# quantizer-main.net
KiCad netlist of a schematic drawn in EAGLE
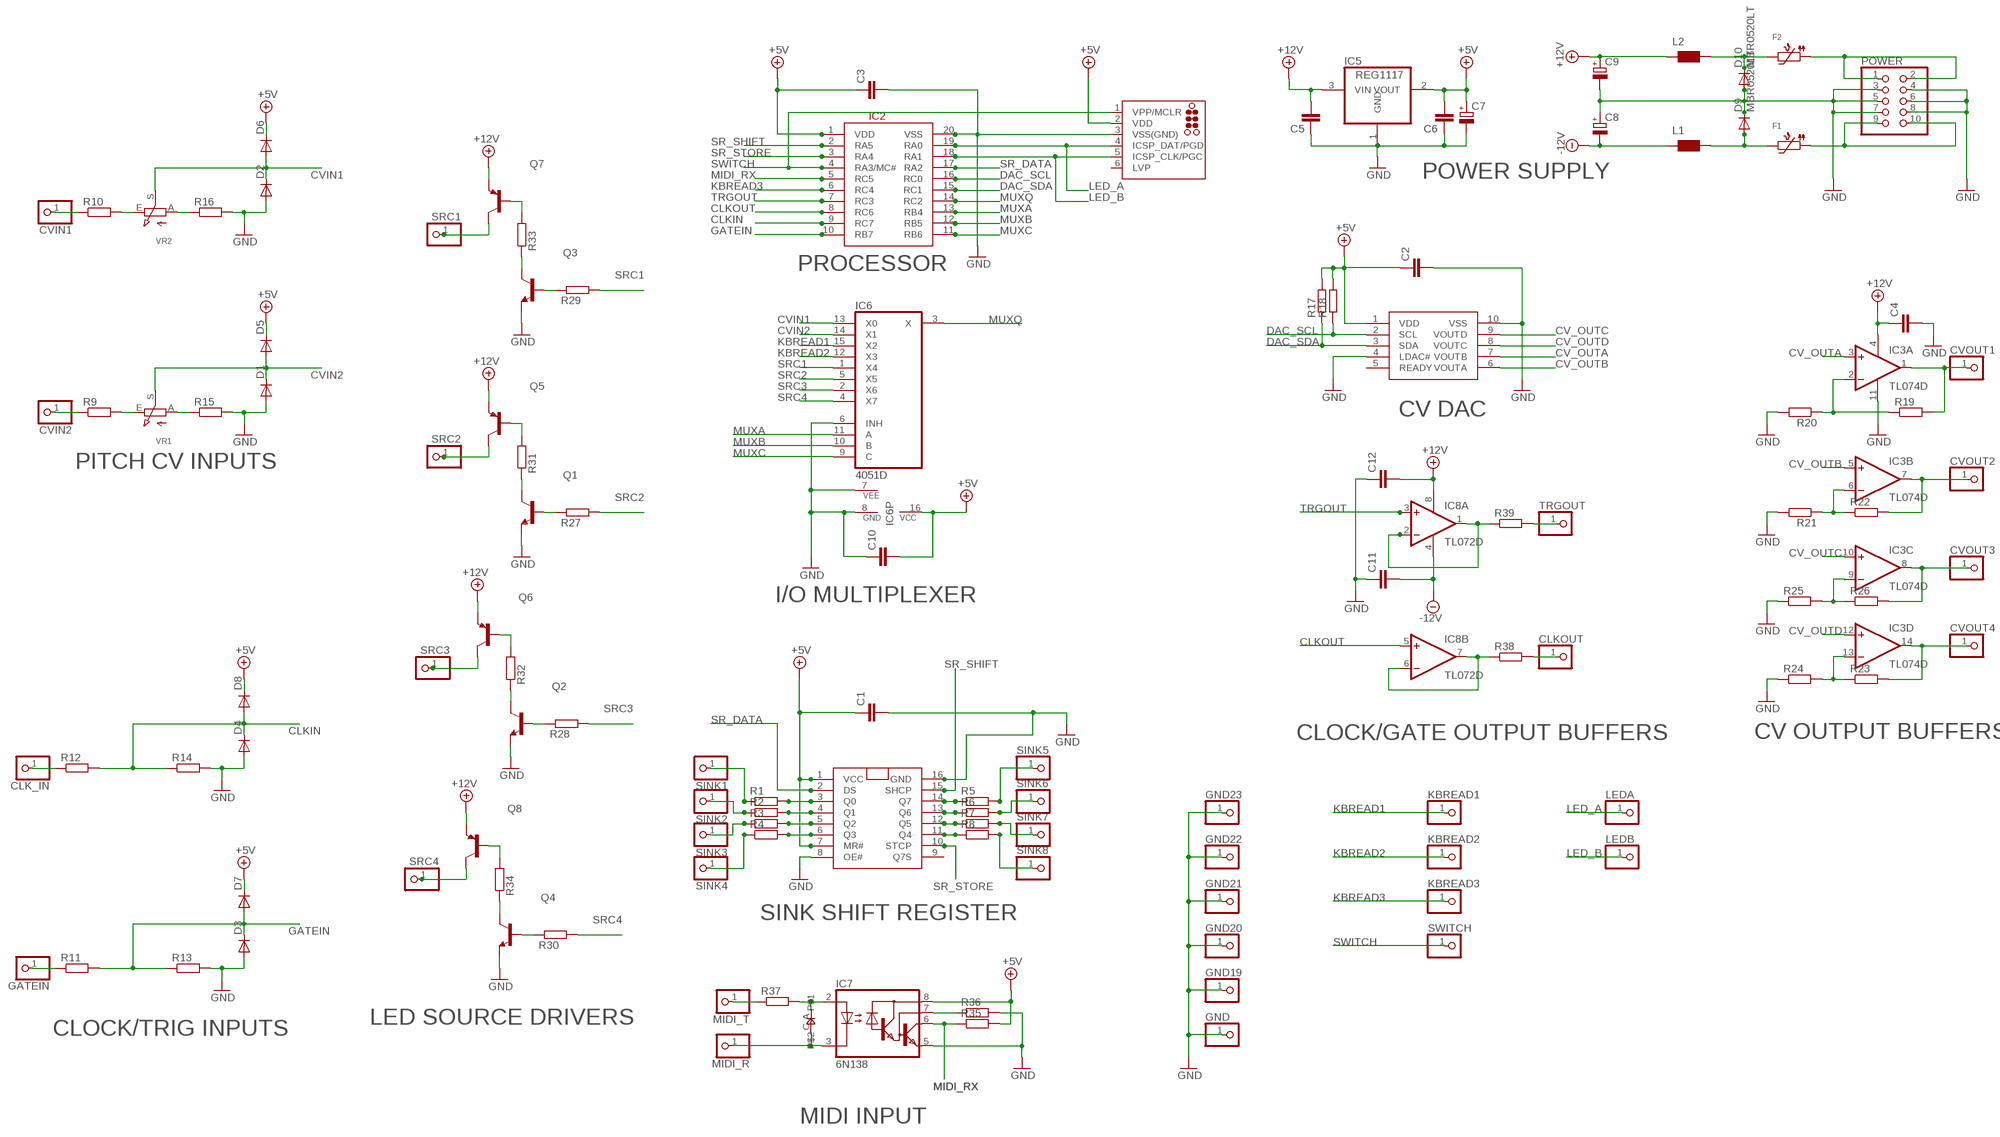
[diagram p0: schematic, sheet 1]

(export (version "E")
  (design (tool "Eeschema 10.0.6"))
  (components
    (comp (ref "C1")
      (value "C-EUC0805")
      (footprint "eagle-import:C0805")
      (libsource (lib "eagle-import") (part "C-EUC0805"))
    )
    (comp (ref "C2")
      (value "C-EUC0805")
      (footprint "eagle-import:C0805")
      (libsource (lib "eagle-import") (part "C-EUC0805"))
    )
    (comp (ref "C3")
      (value "C-EUC0805")
      (footprint "eagle-import:C0805")
      (libsource (lib "eagle-import") (part "C-EUC0805"))
    )
    (comp (ref "C4")
      (value "C-EUC0805")
      (footprint "eagle-import:C0805")
      (libsource (lib "eagle-import") (part "C-EUC0805"))
    )
    (comp (ref "C5")
      (value "C-EUC0805")
      (footprint "eagle-import:C0805")
      (libsource (lib "eagle-import") (part "C-EUC0805"))
    )
    (comp (ref "C6")
      (value "C-EUC0805")
      (footprint "eagle-import:C0805")
      (libsource (lib "eagle-import") (part "C-EUC0805"))
    )
    (comp (ref "C7")
      (value "CPOL-EUE2.5-5")
      (footprint "eagle-import:E2,5-5")
      (libsource (lib "eagle-import") (part "CPOL-EUE2.5-5"))
    )
    (comp (ref "C8")
      (value "CPOL-EUE2.5-7")
      (footprint "eagle-import:E2,5-7")
      (libsource (lib "eagle-import") (part "CPOL-EUE2.5-7"))
    )
    (comp (ref "C9")
      (value "CPOL-EUE2.5-7")
      (footprint "eagle-import:E2,5-7")
      (libsource (lib "eagle-import") (part "CPOL-EUE2.5-7"))
    )
    (comp (ref "C10")
      (value "C-EUC0805")
      (footprint "eagle-import:C0805")
      (libsource (lib "eagle-import") (part "C-EUC0805"))
    )
    (comp (ref "C11")
      (value "C-EUC0805")
      (footprint "eagle-import:C0805")
      (libsource (lib "eagle-import") (part "C-EUC0805"))
    )
    (comp (ref "C12")
      (value "C-EUC0805")
      (footprint "eagle-import:C0805")
      (libsource (lib "eagle-import") (part "C-EUC0805"))
    )
    (comp (ref "CLKOUT")
      (value "PINHD-1X1")
      (footprint "eagle-import:1X01")
      (libsource (lib "eagle-import") (part "PINHD-1X1"))
    )
    (comp (ref "CLK_IN")
      (value "PINHD-1X1")
      (footprint "eagle-import:1X01")
      (libsource (lib "eagle-import") (part "PINHD-1X1"))
    )
    (comp (ref "CVIN1")
      (value "PINHD-1X1")
      (footprint "eagle-import:1X01")
      (libsource (lib "eagle-import") (part "PINHD-1X1"))
    )
    (comp (ref "CVIN2")
      (value "PINHD-1X1")
      (footprint "eagle-import:1X01")
      (libsource (lib "eagle-import") (part "PINHD-1X1"))
    )
    (comp (ref "CVOUT1")
      (value "PINHD-1X1")
      (footprint "eagle-import:1X01")
      (libsource (lib "eagle-import") (part "PINHD-1X1"))
    )
    (comp (ref "CVOUT2")
      (value "PINHD-1X1")
      (footprint "eagle-import:1X01")
      (libsource (lib "eagle-import") (part "PINHD-1X1"))
    )
    (comp (ref "CVOUT3")
      (value "PINHD-1X1")
      (footprint "eagle-import:1X01")
      (libsource (lib "eagle-import") (part "PINHD-1X1"))
    )
    (comp (ref "CVOUT4")
      (value "PINHD-1X1")
      (footprint "eagle-import:1X01")
      (libsource (lib "eagle-import") (part "PINHD-1X1"))
    )
    (comp (ref "D1")
      (value "DIODE-SOD123")
      (footprint "eagle-import:SOD123")
      (libsource (lib "eagle-import") (part "DIODE-SOD123"))
    )
    (comp (ref "D2")
      (value "DIODE-SOD123")
      (footprint "eagle-import:SOD123")
      (libsource (lib "eagle-import") (part "DIODE-SOD123"))
    )
    (comp (ref "D3")
      (value "DIODE-SOD123")
      (footprint "eagle-import:SOD123")
      (libsource (lib "eagle-import") (part "DIODE-SOD123"))
    )
    (comp (ref "D4")
      (value "DIODE-SOD123")
      (footprint "eagle-import:SOD123")
      (libsource (lib "eagle-import") (part "DIODE-SOD123"))
    )
    (comp (ref "D5")
      (value "DIODE-SOD123")
      (footprint "eagle-import:SOD123")
      (libsource (lib "eagle-import") (part "DIODE-SOD123"))
    )
    (comp (ref "D6")
      (value "DIODE-SOD123")
      (footprint "eagle-import:SOD123")
      (libsource (lib "eagle-import") (part "DIODE-SOD123"))
    )
    (comp (ref "D7")
      (value "DIODE-SOD123")
      (footprint "eagle-import:SOD123")
      (libsource (lib "eagle-import") (part "DIODE-SOD123"))
    )
    (comp (ref "D8")
      (value "DIODE-SOD123")
      (footprint "eagle-import:SOD123")
      (libsource (lib "eagle-import") (part "DIODE-SOD123"))
    )
    (comp (ref "D9")
      (value "MBR0520LT")
      (footprint "eagle-import:SOD123")
      (libsource (lib "eagle-import") (part "MBR0520LT"))
    )
    (comp (ref "D10")
      (value "MBR0520LT")
      (footprint "eagle-import:SOD123")
      (libsource (lib "eagle-import") (part "MBR0520LT"))
    )
    (comp (ref "D11")
      (value "0805DIODE")
      (footprint "eagle-import:0805DIODE")
      (libsource (lib "eagle-import") (part "0805DIODE"))
    )
    (comp (ref "F1")
      (value "PTC1210")
      (footprint "eagle-import:PTC1210")
      (libsource (lib "eagle-import") (part "PTC1210"))
    )
    (comp (ref "F2")
      (value "PTC1210")
      (footprint "eagle-import:PTC1210")
      (libsource (lib "eagle-import") (part "PTC1210"))
    )
    (comp (ref "GATEIN")
      (value "PINHD-1X1")
      (footprint "eagle-import:1X01")
      (libsource (lib "eagle-import") (part "PINHD-1X1"))
    )
    (comp (ref "GND")
      (value "PINHD-1X1")
      (footprint "eagle-import:1X01")
      (libsource (lib "eagle-import") (part "PINHD-1X1"))
    )
    (comp (ref "GND19")
      (value "PINHD-1X1")
      (footprint "eagle-import:1X01")
      (libsource (lib "eagle-import") (part "PINHD-1X1"))
    )
    (comp (ref "GND20")
      (value "PINHD-1X1")
      (footprint "eagle-import:1X01")
      (libsource (lib "eagle-import") (part "PINHD-1X1"))
    )
    (comp (ref "GND21")
      (value "PINHD-1X1")
      (footprint "eagle-import:1X01")
      (libsource (lib "eagle-import") (part "PINHD-1X1"))
    )
    (comp (ref "GND22")
      (value "PINHD-1X1")
      (footprint "eagle-import:1X01")
      (libsource (lib "eagle-import") (part "PINHD-1X1"))
    )
    (comp (ref "GND23")
      (value "PINHD-1X1")
      (footprint "eagle-import:1X01")
      (libsource (lib "eagle-import") (part "PINHD-1X1"))
    )
    (comp (ref "IC1")
      (value "NPIC6C596")
      (footprint "eagle-import:SO16")
      (libsource (lib "eagle-import") (part "NPIC6C596"))
    )
    (comp (ref "IC2")
      (value "PIC16F1829SOIC")
      (footprint "eagle-import:SO20W")
      (libsource (lib "eagle-import") (part "PIC16F1829SOIC"))
    )
    (comp (ref "IC3")
      (value "TL074D")
      (footprint "eagle-import:SO14")
      (libsource (lib "eagle-import") (part "TL074D"))
    )
    (comp (ref "IC4")
      (value "MCP4728_QUAD_DAC")
      (footprint "eagle-import:MSOP10")
      (libsource (lib "eagle-import") (part "MCP4728_QUAD_DAC"))
    )
    (comp (ref "IC5")
      (value "REG1117")
      (footprint "eagle-import:SOT223")
      (libsource (lib "eagle-import") (part "REG1117"))
    )
    (comp (ref "IC6")
      (value "4051D")
      (footprint "eagle-import:SO16")
      (libsource (lib "eagle-import") (part "4051D"))
    )
    (comp (ref "IC7")
      (value "6N138")
      (footprint "eagle-import:DIL08")
      (fields (field (name "MF") "VISHAY/TELEFUNKEN"))
      (libsource (lib "eagle-import") (part "6N138"))
    )
    (comp (ref "IC8")
      (value "TL072D")
      (footprint "eagle-import:SO08")
      (libsource (lib "eagle-import") (part "TL072D"))
    )
    (comp (ref "J1")
      (value "TC2030-MCP-NL")
      (footprint "eagle-import:TC2030-MCP-NL")
      (libsource (lib "eagle-import") (part "TC2030-MCP-NL"))
    )
    (comp (ref "KBREAD1")
      (value "PINHD-1X1")
      (footprint "eagle-import:1X01")
      (libsource (lib "eagle-import") (part "PINHD-1X1"))
    )
    (comp (ref "KBREAD2")
      (value "PINHD-1X1")
      (footprint "eagle-import:1X01")
      (libsource (lib "eagle-import") (part "PINHD-1X1"))
    )
    (comp (ref "KBREAD3")
      (value "PINHD-1X1")
      (footprint "eagle-import:1X01")
      (libsource (lib "eagle-import") (part "PINHD-1X1"))
    )
    (comp (ref "L1")
      (value "WE-CBF_0805")
      (footprint "eagle-import:0805")
      (libsource (lib "eagle-import") (part "WE-CBF_0805"))
    )
    (comp (ref "L2")
      (value "WE-CBF_0805")
      (footprint "eagle-import:0805")
      (libsource (lib "eagle-import") (part "WE-CBF_0805"))
    )
    (comp (ref "LEDA")
      (value "PINHD-1X1")
      (footprint "eagle-import:1X01")
      (libsource (lib "eagle-import") (part "PINHD-1X1"))
    )
    (comp (ref "LEDB")
      (value "PINHD-1X1")
      (footprint "eagle-import:1X01")
      (libsource (lib "eagle-import") (part "PINHD-1X1"))
    )
    (comp (ref "MIDI_R")
      (value "PINHD-1X1")
      (footprint "eagle-import:1X01")
      (libsource (lib "eagle-import") (part "PINHD-1X1"))
    )
    (comp (ref "MIDI_T")
      (value "PINHD-1X1")
      (footprint "eagle-import:1X01")
      (libsource (lib "eagle-import") (part "PINHD-1X1"))
    )
    (comp (ref "POWER")
      (value "PINHD-2X5")
      (footprint "eagle-import:2X05")
      (libsource (lib "eagle-import") (part "PINHD-2X5"))
    )
    (comp (ref "Q1")
      (value "MMBT3904LT1-NPN-SOT23-BEC")
      (footprint "eagle-import:SOT23-BEC")
      (libsource (lib "eagle-import") (part "-NPN-SOT23-BECMMBT3904LT1"))
    )
    (comp (ref "Q2")
      (value "MMBT3904LT1-NPN-SOT23-BEC")
      (footprint "eagle-import:SOT23-BEC")
      (libsource (lib "eagle-import") (part "-NPN-SOT23-BECMMBT3904LT1"))
    )
    (comp (ref "Q3")
      (value "MMBT3904LT1-NPN-SOT23-BEC")
      (footprint "eagle-import:SOT23-BEC")
      (libsource (lib "eagle-import") (part "-NPN-SOT23-BECMMBT3904LT1"))
    )
    (comp (ref "Q4")
      (value "MMBT3904LT1-NPN-SOT23-BEC")
      (footprint "eagle-import:SOT23-BEC")
      (libsource (lib "eagle-import") (part "-NPN-SOT23-BECMMBT3904LT1"))
    )
    (comp (ref "Q5")
      (value "MMBT3906LT1-PNP-SOT23-BEC")
      (footprint "eagle-import:SOT23-BEC")
      (libsource (lib "eagle-import") (part "-PNP-SOT23-BECMMBT3906LT1"))
    )
    (comp (ref "Q6")
      (value "MMBT3906LT1-PNP-SOT23-BEC")
      (footprint "eagle-import:SOT23-BEC")
      (libsource (lib "eagle-import") (part "-PNP-SOT23-BECMMBT3906LT1"))
    )
    (comp (ref "Q7")
      (value "MMBT3906LT1-PNP-SOT23-BEC")
      (footprint "eagle-import:SOT23-BEC")
      (libsource (lib "eagle-import") (part "-PNP-SOT23-BECMMBT3906LT1"))
    )
    (comp (ref "Q8")
      (value "MMBT3906LT1-PNP-SOT23-BEC")
      (footprint "eagle-import:SOT23-BEC")
      (libsource (lib "eagle-import") (part "-PNP-SOT23-BECMMBT3906LT1"))
    )
    (comp (ref "R1")
      (value "R-EU_R0805")
      (footprint "eagle-import:R0805")
      (libsource (lib "eagle-import") (part "R-EU_R0805"))
    )
    (comp (ref "R2")
      (value "R-EU_R0805")
      (footprint "eagle-import:R0805")
      (libsource (lib "eagle-import") (part "R-EU_R0805"))
    )
    (comp (ref "R3")
      (value "R-EU_R0805")
      (footprint "eagle-import:R0805")
      (libsource (lib "eagle-import") (part "R-EU_R0805"))
    )
    (comp (ref "R4")
      (value "R-EU_R0805")
      (footprint "eagle-import:R0805")
      (libsource (lib "eagle-import") (part "R-EU_R0805"))
    )
    (comp (ref "R5")
      (value "R-EU_R0805")
      (footprint "eagle-import:R0805")
      (libsource (lib "eagle-import") (part "R-EU_R0805"))
    )
    (comp (ref "R6")
      (value "R-EU_R0805")
      (footprint "eagle-import:R0805")
      (libsource (lib "eagle-import") (part "R-EU_R0805"))
    )
    (comp (ref "R7")
      (value "R-EU_R0805")
      (footprint "eagle-import:R0805")
      (libsource (lib "eagle-import") (part "R-EU_R0805"))
    )
    (comp (ref "R8")
      (value "R-EU_R0805")
      (footprint "eagle-import:R0805")
      (libsource (lib "eagle-import") (part "R-EU_R0805"))
    )
    (comp (ref "R9")
      (value "R-EU_R0805")
      (footprint "eagle-import:R0805")
      (libsource (lib "eagle-import") (part "R-EU_R0805"))
    )
    (comp (ref "R10")
      (value "R-EU_R0805")
      (footprint "eagle-import:R0805")
      (libsource (lib "eagle-import") (part "R-EU_R0805"))
    )
    (comp (ref "R11")
      (value "R-EU_R0805")
      (footprint "eagle-import:R0805")
      (libsource (lib "eagle-import") (part "R-EU_R0805"))
    )
    (comp (ref "R12")
      (value "R-EU_R0805")
      (footprint "eagle-import:R0805")
      (libsource (lib "eagle-import") (part "R-EU_R0805"))
    )
    (comp (ref "R13")
      (value "R-EU_R0805")
      (footprint "eagle-import:R0805")
      (libsource (lib "eagle-import") (part "R-EU_R0805"))
    )
    (comp (ref "R14")
      (value "R-EU_R0805")
      (footprint "eagle-import:R0805")
      (libsource (lib "eagle-import") (part "R-EU_R0805"))
    )
    (comp (ref "R15")
      (value "R-EU_R0805")
      (footprint "eagle-import:R0805")
      (libsource (lib "eagle-import") (part "R-EU_R0805"))
    )
    (comp (ref "R16")
      (value "R-EU_R0805")
      (footprint "eagle-import:R0805")
      (libsource (lib "eagle-import") (part "R-EU_R0805"))
    )
    (comp (ref "R17")
      (value "R-EU_R0805")
      (footprint "eagle-import:R0805")
      (libsource (lib "eagle-import") (part "R-EU_R0805"))
    )
    (comp (ref "R18")
      (value "R-EU_R0805")
      (footprint "eagle-import:R0805")
      (libsource (lib "eagle-import") (part "R-EU_R0805"))
    )
    (comp (ref "R19")
      (value "R-EU_R0805")
      (footprint "eagle-import:R0805")
      (libsource (lib "eagle-import") (part "R-EU_R0805"))
    )
    (comp (ref "R20")
      (value "R-EU_R0805")
      (footprint "eagle-import:R0805")
      (libsource (lib "eagle-import") (part "R-EU_R0805"))
    )
    (comp (ref "R21")
      (value "R-EU_R0805")
      (footprint "eagle-import:R0805")
      (libsource (lib "eagle-import") (part "R-EU_R0805"))
    )
    (comp (ref "R22")
      (value "R-EU_R0805")
      (footprint "eagle-import:R0805")
      (libsource (lib "eagle-import") (part "R-EU_R0805"))
    )
    (comp (ref "R23")
      (value "R-EU_R0805")
      (footprint "eagle-import:R0805")
      (libsource (lib "eagle-import") (part "R-EU_R0805"))
    )
    (comp (ref "R24")
      (value "R-EU_R0805")
      (footprint "eagle-import:R0805")
      (libsource (lib "eagle-import") (part "R-EU_R0805"))
    )
    (comp (ref "R25")
      (value "R-EU_R0805")
      (footprint "eagle-import:R0805")
      (libsource (lib "eagle-import") (part "R-EU_R0805"))
    )
    (comp (ref "R26")
      (value "R-EU_R0805")
      (footprint "eagle-import:R0805")
      (libsource (lib "eagle-import") (part "R-EU_R0805"))
    )
    (comp (ref "R27")
      (value "R-EU_R0805")
      (footprint "eagle-import:R0805")
      (libsource (lib "eagle-import") (part "R-EU_R0805"))
    )
    (comp (ref "R28")
      (value "R-EU_R0805")
      (footprint "eagle-import:R0805")
      (libsource (lib "eagle-import") (part "R-EU_R0805"))
    )
    (comp (ref "R29")
      (value "R-EU_R0805")
      (footprint "eagle-import:R0805")
      (libsource (lib "eagle-import") (part "R-EU_R0805"))
    )
    (comp (ref "R30")
      (value "R-EU_R0805")
      (footprint "eagle-import:R0805")
      (libsource (lib "eagle-import") (part "R-EU_R0805"))
    )
    (comp (ref "R31")
      (value "R-EU_R0805")
      (footprint "eagle-import:R0805")
      (libsource (lib "eagle-import") (part "R-EU_R0805"))
    )
    (comp (ref "R32")
      (value "R-EU_R0805")
      (footprint "eagle-import:R0805")
      (libsource (lib "eagle-import") (part "R-EU_R0805"))
    )
    (comp (ref "R33")
      (value "R-EU_R0805")
      (footprint "eagle-import:R0805")
      (libsource (lib "eagle-import") (part "R-EU_R0805"))
    )
    (comp (ref "R34")
      (value "R-EU_R0805")
      (footprint "eagle-import:R0805")
      (libsource (lib "eagle-import") (part "R-EU_R0805"))
    )
    (comp (ref "R35")
      (value "R-EU_R0805")
      (footprint "eagle-import:R0805")
      (libsource (lib "eagle-import") (part "R-EU_R0805"))
    )
    (comp (ref "R36")
      (value "R-EU_R0805")
      (footprint "eagle-import:R0805")
      (libsource (lib "eagle-import") (part "R-EU_R0805"))
    )
    (comp (ref "R37")
      (value "R-EU_R0805")
      (footprint "eagle-import:R0805")
      (libsource (lib "eagle-import") (part "R-EU_R0805"))
    )
    (comp (ref "R38")
      (value "R-EU_R0805")
      (footprint "eagle-import:R0805")
      (libsource (lib "eagle-import") (part "R-EU_R0805"))
    )
    (comp (ref "R39")
      (value "R-EU_R0805")
      (footprint "eagle-import:R0805")
      (libsource (lib "eagle-import") (part "R-EU_R0805"))
    )
    (comp (ref "SINK1")
      (value "PINHD-1X1")
      (footprint "eagle-import:1X01")
      (libsource (lib "eagle-import") (part "PINHD-1X1"))
    )
    (comp (ref "SINK2")
      (value "PINHD-1X1")
      (footprint "eagle-import:1X01")
      (libsource (lib "eagle-import") (part "PINHD-1X1"))
    )
    (comp (ref "SINK3")
      (value "PINHD-1X1")
      (footprint "eagle-import:1X01")
      (libsource (lib "eagle-import") (part "PINHD-1X1"))
    )
    (comp (ref "SINK4")
      (value "PINHD-1X1")
      (footprint "eagle-import:1X01")
      (libsource (lib "eagle-import") (part "PINHD-1X1"))
    )
    (comp (ref "SINK5")
      (value "PINHD-1X1")
      (footprint "eagle-import:1X01")
      (libsource (lib "eagle-import") (part "PINHD-1X1"))
    )
    (comp (ref "SINK6")
      (value "PINHD-1X1")
      (footprint "eagle-import:1X01")
      (libsource (lib "eagle-import") (part "PINHD-1X1"))
    )
    (comp (ref "SINK7")
      (value "PINHD-1X1")
      (footprint "eagle-import:1X01")
      (libsource (lib "eagle-import") (part "PINHD-1X1"))
    )
    (comp (ref "SINK8")
      (value "PINHD-1X1")
      (footprint "eagle-import:1X01")
      (libsource (lib "eagle-import") (part "PINHD-1X1"))
    )
    (comp (ref "SRC1")
      (value "PINHD-1X1")
      (footprint "eagle-import:1X01")
      (libsource (lib "eagle-import") (part "PINHD-1X1"))
    )
    (comp (ref "SRC2")
      (value "PINHD-1X1")
      (footprint "eagle-import:1X01")
      (libsource (lib "eagle-import") (part "PINHD-1X1"))
    )
    (comp (ref "SRC3")
      (value "PINHD-1X1")
      (footprint "eagle-import:1X01")
      (libsource (lib "eagle-import") (part "PINHD-1X1"))
    )
    (comp (ref "SRC4")
      (value "PINHD-1X1")
      (footprint "eagle-import:1X01")
      (libsource (lib "eagle-import") (part "PINHD-1X1"))
    )
    (comp (ref "SWITCH")
      (value "PINHD-1X1")
      (footprint "eagle-import:1X01")
      (libsource (lib "eagle-import") (part "PINHD-1X1"))
    )
    (comp (ref "TRGOUT")
      (value "PINHD-1X1")
      (footprint "eagle-import:1X01")
      (libsource (lib "eagle-import") (part "PINHD-1X1"))
    )
    (comp (ref "VR1")
      (value "TRIMPOT10K_BOURNS")
      (footprint "eagle-import:TRIMPOT_BOURNS3MM")
      (libsource (lib "eagle-import") (part "TRIMPOT10K_BOURNS"))
    )
    (comp (ref "VR2")
      (value "TRIMPOT10K_BOURNS")
      (footprint "eagle-import:TRIMPOT_BOURNS3MM")
      (libsource (lib "eagle-import") (part "TRIMPOT10K_BOURNS"))
    )
  )
  (nets
    (net (code "1") (name "+5V") (class "Default")
      (node (ref "C1") (pin "1") (pinfunction "1_1") (pintype "passive"))
      (node (ref "C10") (pin "2") (pinfunction "2_2") (pintype "passive"))
      (node (ref "C2") (pin "1") (pinfunction "1_1") (pintype "passive"))
      (node (ref "C3") (pin "1") (pinfunction "1_1") (pintype "passive"))
      (node (ref "C6") (pin "2") (pinfunction "2_2") (pintype "passive"))
      (node (ref "C7") (pin "+") (pinfunction "+_+") (pintype "passive"))
      (node (ref "D5") (pin "C") (pinfunction "C_C") (pintype "passive"))
      (node (ref "D6") (pin "C") (pinfunction "C_C") (pintype "passive"))
      (node (ref "D7") (pin "C") (pinfunction "C_C") (pintype "passive"))
      (node (ref "D8") (pin "C") (pinfunction "C_C") (pintype "passive"))
      (node (ref "IC1") (pin "1") (pinfunction "VCC_1") (pintype "power_in"))
      (node (ref "IC1") (pin "7") (pinfunction "MR#_7") (pintype "input"))
      (node (ref "IC2") (pin "1") (pinfunction "VDD_1") (pintype "power_in"))
      (node (ref "IC4") (pin "1") (pinfunction "VDD_1") (pintype "power_in"))
      (node (ref "IC5") (pin "2") (pinfunction "VOUT_2") (pintype "output"))
      (node (ref "IC6") (pin "16") (pinfunction "VCC_16") (pintype "power_in"))
      (node (ref "IC7") (pin "8") (pinfunction "VCC_8") (pintype "passive"))
      (node (ref "J1") (pin "2") (pinfunction "VDD_2") (pintype "power_in"))
      (node (ref "R17") (pin "2") (pinfunction "2_2") (pintype "passive"))
      (node (ref "R18") (pin "2") (pinfunction "2_2") (pintype "passive"))
      (node (ref "R35") (pin "2") (pinfunction "2_2") (pintype "passive"))
    )
    (net (code "2") (name "+12V") (class "Default")
      (node (ref "C12") (pin "2") (pinfunction "2_2") (pintype "passive"))
      (node (ref "C4") (pin "1") (pinfunction "1_1") (pintype "passive"))
      (node (ref "C5") (pin "2") (pinfunction "2_2") (pintype "passive"))
      (node (ref "C9") (pin "+") (pinfunction "+_+") (pintype "passive"))
      (node (ref "IC3") (pin "4") (pinfunction "V+_4") (pintype "power_in"))
      (node (ref "IC5") (pin "3") (pinfunction "VIN_3") (pintype "input"))
      (node (ref "IC8") (pin "8") (pinfunction "V+_8") (pintype "power_in"))
      (node (ref "L2") (pin "1") (pinfunction "1_1") (pintype "passive"))
      (node (ref "Q5") (pin "E") (pinfunction "E_E") (pintype "passive"))
      (node (ref "Q6") (pin "E") (pinfunction "E_E") (pintype "passive"))
      (node (ref "Q7") (pin "E") (pinfunction "E_E") (pintype "passive"))
      (node (ref "Q8") (pin "E") (pinfunction "E_E") (pintype "passive"))
    )
    (net (code "3") (name "-12V") (class "Default")
      (node (ref "C11") (pin "2") (pinfunction "2_2") (pintype "passive"))
      (node (ref "C8") (pin "-") (pinfunction "-_-") (pintype "passive"))
      (node (ref "IC8") (pin "4") (pinfunction "V-_4") (pintype "power_in"))
      (node (ref "L1") (pin "1") (pinfunction "1_1") (pintype "passive"))
    )
    (net (code "4") (name "/CLKIN") (class "Default")
      (node (ref "D4") (pin "C") (pinfunction "C_C") (pintype "passive"))
      (node (ref "D8") (pin "A") (pinfunction "A_A") (pintype "passive"))
      (node (ref "IC2") (pin "9") (pinfunction "RC7_9") (pintype "bidirectional"))
      (node (ref "R12") (pin "2") (pinfunction "2_2") (pintype "passive"))
      (node (ref "R14") (pin "1") (pinfunction "1_1") (pintype "passive"))
    )
    (net (code "5") (name "/CLKOUT") (class "Default")
      (node (ref "IC2") (pin "8") (pinfunction "RC6_8") (pintype "bidirectional"))
      (node (ref "IC8") (pin "5") (pinfunction "+IN_5") (pintype "input"))
    )
    (net (code "6") (name "/CVIN1") (class "Default")
      (node (ref "D2") (pin "C") (pinfunction "C_C") (pintype "passive"))
      (node (ref "D6") (pin "A") (pinfunction "A_A") (pintype "passive"))
      (node (ref "IC6") (pin "13") (pinfunction "X0_13") (pintype "bidirectional"))
      (node (ref "VR2") (pin "S") (pinfunction "S_S") (pintype "passive"))
    )
    (net (code "7") (name "/CVIN2") (class "Default")
      (node (ref "D1") (pin "C") (pinfunction "C_C") (pintype "passive"))
      (node (ref "D5") (pin "A") (pinfunction "A_A") (pintype "passive"))
      (node (ref "IC6") (pin "14") (pinfunction "X1_14") (pintype "bidirectional"))
      (node (ref "VR1") (pin "S") (pinfunction "S_S") (pintype "passive"))
    )
    (net (code "8") (name "/CV_OUTA") (class "Default")
      (node (ref "IC3") (pin "3") (pinfunction "+IN_3") (pintype "input"))
      (node (ref "IC4") (pin "7") (pinfunction "VOUTB_7") (pintype "bidirectional"))
    )
    (net (code "9") (name "/CV_OUTB") (class "Default")
      (node (ref "IC3") (pin "5") (pinfunction "+IN_5") (pintype "input"))
      (node (ref "IC4") (pin "6") (pinfunction "VOUTA_6") (pintype "bidirectional"))
    )
    (net (code "10") (name "/CV_OUTC") (class "Default")
      (node (ref "IC3") (pin "10") (pinfunction "+IN_10") (pintype "input"))
      (node (ref "IC4") (pin "9") (pinfunction "VOUTD_9") (pintype "bidirectional"))
    )
    (net (code "11") (name "/CV_OUTD") (class "Default")
      (node (ref "IC3") (pin "12") (pinfunction "+IN_12") (pintype "input"))
      (node (ref "IC4") (pin "8") (pinfunction "VOUTC_8") (pintype "bidirectional"))
    )
    (net (code "12") (name "/DAC_SCL") (class "Default")
      (node (ref "IC2") (pin "16") (pinfunction "RC0_16") (pintype "bidirectional"))
      (node (ref "IC4") (pin "2") (pinfunction "SCL_2") (pintype "bidirectional"))
      (node (ref "R18") (pin "1") (pinfunction "1_1") (pintype "passive"))
    )
    (net (code "13") (name "/DAC_SDA") (class "Default")
      (node (ref "IC2") (pin "15") (pinfunction "RC1_15") (pintype "bidirectional"))
      (node (ref "IC4") (pin "3") (pinfunction "SDA_3") (pintype "bidirectional"))
      (node (ref "R17") (pin "1") (pinfunction "1_1") (pintype "passive"))
    )
    (net (code "14") (name "/GATEIN") (class "Default")
      (node (ref "D3") (pin "C") (pinfunction "C_C") (pintype "passive"))
      (node (ref "D7") (pin "A") (pinfunction "A_A") (pintype "passive"))
      (node (ref "IC2") (pin "10") (pinfunction "RB7_10") (pintype "bidirectional"))
      (node (ref "R11") (pin "2") (pinfunction "2_2") (pintype "passive"))
      (node (ref "R13") (pin "1") (pinfunction "1_1") (pintype "passive"))
    )
    (net (code "15") (name "/KBREAD1") (class "Default")
      (node (ref "IC6") (pin "15") (pinfunction "X2_15") (pintype "bidirectional"))
      (node (ref "KBREAD1") (pin "1") (pinfunction "1_1") (pintype "passive"))
    )
    (net (code "16") (name "/KBREAD2") (class "Default")
      (node (ref "IC6") (pin "12") (pinfunction "X3_12") (pintype "bidirectional"))
      (node (ref "KBREAD2") (pin "1") (pinfunction "1_1") (pintype "passive"))
    )
    (net (code "17") (name "/KBREAD3") (class "Default")
      (node (ref "IC2") (pin "6") (pinfunction "RC4_6") (pintype "bidirectional"))
      (node (ref "KBREAD3") (pin "1") (pinfunction "1_1") (pintype "passive"))
    )
    (net (code "18") (name "/LED_A") (class "Default")
      (node (ref "IC2") (pin "19") (pinfunction "RA0_19") (pintype "bidirectional"))
      (node (ref "J1") (pin "4") (pinfunction "ICSP_DAT/PGD_4") (pintype "bidirectional"))
      (node (ref "LEDA") (pin "1") (pinfunction "1_1") (pintype "passive"))
    )
    (net (code "19") (name "/LED_B") (class "Default")
      (node (ref "IC2") (pin "18") (pinfunction "RA1_18") (pintype "bidirectional"))
      (node (ref "J1") (pin "5") (pinfunction "ICSP_CLK/PGC_5") (pintype "output"))
      (node (ref "LEDB") (pin "1") (pinfunction "1_1") (pintype "passive"))
    )
    (net (code "20") (name "/MIDI_RX") (class "Default")
      (node (ref "IC2") (pin "5") (pinfunction "RC5_5") (pintype "bidirectional"))
      (node (ref "IC7") (pin "6") (pinfunction "VO_6") (pintype "passive"))
      (node (ref "R35") (pin "1") (pinfunction "1_1") (pintype "passive"))
    )
    (net (code "21") (name "/MUXA") (class "Default")
      (node (ref "IC2") (pin "13") (pinfunction "RB4_13") (pintype "bidirectional"))
      (node (ref "IC6") (pin "11") (pinfunction "A_11") (pintype "input"))
    )
    (net (code "22") (name "/MUXB") (class "Default")
      (node (ref "IC2") (pin "12") (pinfunction "RB5_12") (pintype "bidirectional"))
      (node (ref "IC6") (pin "10") (pinfunction "B_10") (pintype "input"))
    )
    (net (code "23") (name "/MUXC") (class "Default")
      (node (ref "IC2") (pin "11") (pinfunction "RB6_11") (pintype "bidirectional"))
      (node (ref "IC6") (pin "9") (pinfunction "C_9") (pintype "input"))
    )
    (net (code "24") (name "/MUXQ") (class "Default")
      (node (ref "IC2") (pin "14") (pinfunction "RC2_14") (pintype "bidirectional"))
      (node (ref "IC6") (pin "3") (pinfunction "X_3") (pintype "bidirectional"))
    )
    (net (code "25") (name "/SRC1") (class "Default")
      (node (ref "IC6") (pin "1") (pinfunction "X4_1") (pintype "bidirectional"))
      (node (ref "R29") (pin "2") (pinfunction "2_2") (pintype "passive"))
    )
    (net (code "26") (name "/SRC2") (class "Default")
      (node (ref "IC6") (pin "5") (pinfunction "X5_5") (pintype "bidirectional"))
      (node (ref "R27") (pin "2") (pinfunction "2_2") (pintype "passive"))
    )
    (net (code "27") (name "/SRC3") (class "Default")
      (node (ref "IC6") (pin "2") (pinfunction "X6_2") (pintype "bidirectional"))
      (node (ref "R28") (pin "2") (pinfunction "2_2") (pintype "passive"))
    )
    (net (code "28") (name "/SRC4") (class "Default")
      (node (ref "IC6") (pin "4") (pinfunction "X7_4") (pintype "bidirectional"))
      (node (ref "R30") (pin "2") (pinfunction "2_2") (pintype "passive"))
    )
    (net (code "29") (name "/SR_DATA") (class "Default")
      (node (ref "IC1") (pin "2") (pinfunction "DS_2") (pintype "input"))
      (node (ref "IC2") (pin "17") (pinfunction "RA2_17") (pintype "bidirectional"))
    )
    (net (code "30") (name "/SR_SHIFT") (class "Default")
      (node (ref "IC1") (pin "15") (pinfunction "SHCP_15") (pintype "input"))
      (node (ref "IC2") (pin "2") (pinfunction "RA5_2") (pintype "bidirectional"))
    )
    (net (code "31") (name "/SR_STORE") (class "Default")
      (node (ref "IC1") (pin "10") (pinfunction "STCP_10") (pintype "input"))
      (node (ref "IC2") (pin "3") (pinfunction "RA4_3") (pintype "bidirectional"))
    )
    (net (code "32") (name "/SWITCH") (class "Default")
      (node (ref "IC2") (pin "4") (pinfunction "RA3/MC#_4") (pintype "bidirectional"))
      (node (ref "J1") (pin "1") (pinfunction "VPP/MCLR_1") (pintype "passive"))
      (node (ref "SWITCH") (pin "1") (pinfunction "1_1") (pintype "passive"))
    )
    (net (code "33") (name "/TRGOUT") (class "Default")
      (node (ref "IC2") (pin "7") (pinfunction "RC3_7") (pintype "bidirectional"))
      (node (ref "IC8") (pin "3") (pinfunction "+IN_3") (pintype "input"))
    )
    (net (code "34") (name "GND") (class "Default")
      (node (ref "C1") (pin "2") (pinfunction "2_2") (pintype "passive"))
      (node (ref "C10") (pin "1") (pinfunction "1_1") (pintype "passive"))
      (node (ref "C11") (pin "1") (pinfunction "1_1") (pintype "passive"))
      (node (ref "C12") (pin "1") (pinfunction "1_1") (pintype "passive"))
      (node (ref "C2") (pin "2") (pinfunction "2_2") (pintype "passive"))
      (node (ref "C3") (pin "2") (pinfunction "2_2") (pintype "passive"))
      (node (ref "C4") (pin "2") (pinfunction "2_2") (pintype "passive"))
      (node (ref "C5") (pin "1") (pinfunction "1_1") (pintype "passive"))
      (node (ref "C6") (pin "1") (pinfunction "1_1") (pintype "passive"))
      (node (ref "C7") (pin "-") (pinfunction "-_-") (pintype "passive"))
      (node (ref "C8") (pin "+") (pinfunction "+_+") (pintype "passive"))
      (node (ref "C9") (pin "-") (pinfunction "-_-") (pintype "passive"))
      (node (ref "D1") (pin "A") (pinfunction "A_A") (pintype "passive"))
      (node (ref "D10") (pin "A") (pinfunction "A_A") (pintype "passive"))
      (node (ref "D2") (pin "A") (pinfunction "A_A") (pintype "passive"))
      (node (ref "D3") (pin "A") (pinfunction "A_A") (pintype "passive"))
      (node (ref "D4") (pin "A") (pinfunction "A_A") (pintype "passive"))
      (node (ref "D9") (pin "C") (pinfunction "C_C") (pintype "passive"))
      (node (ref "GND") (pin "1") (pinfunction "1_1") (pintype "passive"))
      (node (ref "GND19") (pin "1") (pinfunction "1_1") (pintype "passive"))
      (node (ref "GND20") (pin "1") (pinfunction "1_1") (pintype "passive"))
      (node (ref "GND21") (pin "1") (pinfunction "1_1") (pintype "passive"))
      (node (ref "GND22") (pin "1") (pinfunction "1_1") (pintype "passive"))
      (node (ref "GND23") (pin "1") (pinfunction "1_1") (pintype "passive"))
      (node (ref "IC1") (pin "16") (pinfunction "GND_16") (pintype "power_in"))
      (node (ref "IC1") (pin "8") (pinfunction "OE#_8") (pintype "input"))
      (node (ref "IC2") (pin "20") (pinfunction "VSS_20") (pintype "power_in"))
      (node (ref "IC3") (pin "11") (pinfunction "V-_11") (pintype "power_in"))
      (node (ref "IC4") (pin "10") (pinfunction "VSS_10") (pintype "power_in"))
      (node (ref "IC4") (pin "4") (pinfunction "LDAC#_4") (pintype "bidirectional"))
      (node (ref "IC5") (pin "1") (pinfunction "GND_1") (pintype "power_in"))
      (node (ref "IC6") (pin "6") (pinfunction "INH_6") (pintype "input"))
      (node (ref "IC6") (pin "7") (pinfunction "VEE_7") (pintype "power_in"))
      (node (ref "IC6") (pin "8") (pinfunction "GND_8") (pintype "power_in"))
      (node (ref "IC7") (pin "5") (pinfunction "GND_5") (pintype "passive"))
      (node (ref "J1") (pin "3") (pinfunction "VSS(GND)_3") (pintype "power_in"))
      (node (ref "POWER") (pin "3") (pinfunction "3_3") (pintype "passive"))
      (node (ref "POWER") (pin "4") (pinfunction "4_4") (pintype "passive"))
      (node (ref "POWER") (pin "5") (pinfunction "5_5") (pintype "passive"))
      (node (ref "POWER") (pin "6") (pinfunction "6_6") (pintype "passive"))
      (node (ref "POWER") (pin "7") (pinfunction "7_7") (pintype "passive"))
      (node (ref "POWER") (pin "8") (pinfunction "8_8") (pintype "passive"))
      (node (ref "Q1") (pin "E") (pinfunction "E_E") (pintype "passive"))
      (node (ref "Q2") (pin "E") (pinfunction "E_E") (pintype "passive"))
      (node (ref "Q3") (pin "E") (pinfunction "E_E") (pintype "passive"))
      (node (ref "Q4") (pin "E") (pinfunction "E_E") (pintype "passive"))
      (node (ref "R13") (pin "2") (pinfunction "2_2") (pintype "passive"))
      (node (ref "R14") (pin "2") (pinfunction "2_2") (pintype "passive"))
      (node (ref "R15") (pin "2") (pinfunction "2_2") (pintype "passive"))
      (node (ref "R16") (pin "2") (pinfunction "2_2") (pintype "passive"))
      (node (ref "R20") (pin "2") (pinfunction "2_2") (pintype "passive"))
      (node (ref "R21") (pin "2") (pinfunction "2_2") (pintype "passive"))
      (node (ref "R24") (pin "1") (pinfunction "1_1") (pintype "passive"))
      (node (ref "R25") (pin "1") (pinfunction "1_1") (pintype "passive"))
      (node (ref "R36") (pin "2") (pinfunction "2_2") (pintype "passive"))
    )
    (net (code "35") (name "Net-(CLKOUT-Pad1)") (class "Default")
      (node (ref "CLKOUT") (pin "1") (pinfunction "1_1") (pintype "passive"))
      (node (ref "R38") (pin "2") (pinfunction "2_2") (pintype "passive"))
    )
    (net (code "36") (name "Net-(CLK_IN-Pad1)") (class "Default")
      (node (ref "CLK_IN") (pin "1") (pinfunction "1_1") (pintype "passive"))
      (node (ref "R12") (pin "1") (pinfunction "1_1") (pintype "passive"))
    )
    (net (code "37") (name "Net-(CVIN1-Pad1)") (class "Default")
      (node (ref "CVIN1") (pin "1") (pinfunction "1_1") (pintype "passive"))
      (node (ref "R10") (pin "1") (pinfunction "1_1") (pintype "passive"))
    )
    (net (code "38") (name "Net-(CVIN2-Pad1)") (class "Default")
      (node (ref "CVIN2") (pin "1") (pinfunction "1_1") (pintype "passive"))
      (node (ref "R9") (pin "1") (pinfunction "1_1") (pintype "passive"))
    )
    (net (code "39") (name "Net-(D11-P$1)") (class "Default")
      (node (ref "D11") (pin "C") (pinfunction "P$1_C") (pintype "bidirectional"))
      (node (ref "IC7") (pin "3") (pinfunction "C_3") (pintype "passive"))
      (node (ref "MIDI_R") (pin "1") (pinfunction "1_1") (pintype "passive"))
    )
    (net (code "40") (name "Net-(D11-P$2)") (class "Default")
      (node (ref "D11") (pin "A") (pinfunction "P$2_A") (pintype "bidirectional"))
      (node (ref "IC7") (pin "2") (pinfunction "A_2") (pintype "passive"))
      (node (ref "R37") (pin "2") (pinfunction "2_2") (pintype "passive"))
    )
    (net (code "41") (name "Net-(F1-1)") (class "Default")
      (node (ref "F1") (pin "P$1") (pinfunction "1_P$1") (pintype "passive"))
      (node (ref "POWER") (pin "10") (pinfunction "10_10") (pintype "passive"))
      (node (ref "POWER") (pin "9") (pinfunction "9_9") (pintype "passive"))
    )
    (net (code "42") (name "Net-(F1-2)") (class "Default")
      (node (ref "D9") (pin "A") (pinfunction "A_A") (pintype "passive"))
      (node (ref "F1") (pin "P$2") (pinfunction "2_P$2") (pintype "passive"))
      (node (ref "L1") (pin "2") (pinfunction "2_2") (pintype "passive"))
    )
    (net (code "43") (name "Net-(F2-1)") (class "Default")
      (node (ref "F2") (pin "P$1") (pinfunction "1_P$1") (pintype "passive"))
      (node (ref "POWER") (pin "1") (pinfunction "1_1") (pintype "passive"))
      (node (ref "POWER") (pin "2") (pinfunction "2_2") (pintype "passive"))
    )
    (net (code "44") (name "Net-(F2-2)") (class "Default")
      (node (ref "D10") (pin "C") (pinfunction "C_C") (pintype "passive"))
      (node (ref "F2") (pin "P$2") (pinfunction "2_P$2") (pintype "passive"))
      (node (ref "L2") (pin "2") (pinfunction "2_2") (pintype "passive"))
    )
    (net (code "45") (name "Net-(GATEIN-Pad1)") (class "Default")
      (node (ref "GATEIN") (pin "1") (pinfunction "1_1") (pintype "passive"))
      (node (ref "R11") (pin "1") (pinfunction "1_1") (pintype "passive"))
    )
    (net (code "46") (name "Net-(IC1-Q0)") (class "Default")
      (node (ref "IC1") (pin "3") (pinfunction "Q0_3") (pintype "open_collector"))
      (node (ref "R1") (pin "2") (pinfunction "2_2") (pintype "passive"))
    )
    (net (code "47") (name "Net-(IC1-Q1)") (class "Default")
      (node (ref "IC1") (pin "4") (pinfunction "Q1_4") (pintype "open_collector"))
      (node (ref "R2") (pin "2") (pinfunction "2_2") (pintype "passive"))
    )
    (net (code "48") (name "Net-(IC1-Q2)") (class "Default")
      (node (ref "IC1") (pin "5") (pinfunction "Q2_5") (pintype "open_collector"))
      (node (ref "R3") (pin "2") (pinfunction "2_2") (pintype "passive"))
    )
    (net (code "49") (name "Net-(IC1-Q3)") (class "Default")
      (node (ref "IC1") (pin "6") (pinfunction "Q3_6") (pintype "open_collector"))
      (node (ref "R4") (pin "2") (pinfunction "2_2") (pintype "passive"))
    )
    (net (code "50") (name "Net-(IC1-Q4)") (class "Default")
      (node (ref "IC1") (pin "11") (pinfunction "Q4_11") (pintype "open_collector"))
      (node (ref "R8") (pin "1") (pinfunction "1_1") (pintype "passive"))
    )
    (net (code "51") (name "Net-(IC1-Q5)") (class "Default")
      (node (ref "IC1") (pin "12") (pinfunction "Q5_12") (pintype "open_collector"))
      (node (ref "R7") (pin "1") (pinfunction "1_1") (pintype "passive"))
    )
    (net (code "52") (name "Net-(IC1-Q6)") (class "Default")
      (node (ref "IC1") (pin "13") (pinfunction "Q6_13") (pintype "open_collector"))
      (node (ref "R6") (pin "1") (pinfunction "1_1") (pintype "passive"))
    )
    (net (code "53") (name "Net-(IC1-Q7)") (class "Default")
      (node (ref "IC1") (pin "14") (pinfunction "Q7_14") (pintype "open_collector"))
      (node (ref "R5") (pin "1") (pinfunction "1_1") (pintype "passive"))
    )
    (net (code "54") (name "Net-(IC3A--IN)") (class "Default")
      (node (ref "IC3") (pin "2") (pinfunction "-IN_2") (pintype "input"))
      (node (ref "R19") (pin "1") (pinfunction "1_1") (pintype "passive"))
      (node (ref "R20") (pin "1") (pinfunction "1_1") (pintype "passive"))
    )
    (net (code "55") (name "Net-(IC3A-OUT)") (class "Default")
      (node (ref "CVOUT1") (pin "1") (pinfunction "1_1") (pintype "passive"))
      (node (ref "IC3") (pin "1") (pinfunction "OUT_1") (pintype "output"))
      (node (ref "R19") (pin "2") (pinfunction "2_2") (pintype "passive"))
    )
    (net (code "56") (name "Net-(IC3B--IN)") (class "Default")
      (node (ref "IC3") (pin "6") (pinfunction "-IN_6") (pintype "input"))
      (node (ref "R21") (pin "1") (pinfunction "1_1") (pintype "passive"))
      (node (ref "R22") (pin "1") (pinfunction "1_1") (pintype "passive"))
    )
    (net (code "57") (name "Net-(IC3B-OUT)") (class "Default")
      (node (ref "CVOUT2") (pin "1") (pinfunction "1_1") (pintype "passive"))
      (node (ref "IC3") (pin "7") (pinfunction "OUT_7") (pintype "output"))
      (node (ref "R22") (pin "2") (pinfunction "2_2") (pintype "passive"))
    )
    (net (code "58") (name "Net-(IC3C--IN)") (class "Default")
      (node (ref "IC3") (pin "9") (pinfunction "-IN_9") (pintype "input"))
      (node (ref "R25") (pin "2") (pinfunction "2_2") (pintype "passive"))
      (node (ref "R26") (pin "1") (pinfunction "1_1") (pintype "passive"))
    )
    (net (code "59") (name "Net-(IC3C-OUT)") (class "Default")
      (node (ref "CVOUT3") (pin "1") (pinfunction "1_1") (pintype "passive"))
      (node (ref "IC3") (pin "8") (pinfunction "OUT_8") (pintype "output"))
      (node (ref "R26") (pin "2") (pinfunction "2_2") (pintype "passive"))
    )
    (net (code "60") (name "Net-(IC3D--IN)") (class "Default")
      (node (ref "IC3") (pin "13") (pinfunction "-IN_13") (pintype "input"))
      (node (ref "R23") (pin "1") (pinfunction "1_1") (pintype "passive"))
      (node (ref "R24") (pin "2") (pinfunction "2_2") (pintype "passive"))
    )
    (net (code "61") (name "Net-(IC3D-OUT)") (class "Default")
      (node (ref "CVOUT4") (pin "1") (pinfunction "1_1") (pintype "passive"))
      (node (ref "IC3") (pin "14") (pinfunction "OUT_14") (pintype "output"))
      (node (ref "R23") (pin "2") (pinfunction "2_2") (pintype "passive"))
    )
    (net (code "62") (name "Net-(IC7-VB)") (class "Default")
      (node (ref "IC7") (pin "7") (pinfunction "VB_7") (pintype "passive"))
      (node (ref "R36") (pin "1") (pinfunction "1_1") (pintype "passive"))
    )
    (net (code "63") (name "Net-(IC8A--IN)") (class "Default")
      (node (ref "IC8") (pin "1") (pinfunction "OUT_1") (pintype "output"))
      (node (ref "IC8") (pin "2") (pinfunction "-IN_2") (pintype "input"))
      (node (ref "R39") (pin "1") (pinfunction "1_1") (pintype "passive"))
    )
    (net (code "64") (name "Net-(IC8B--IN)") (class "Default")
      (node (ref "IC8") (pin "6") (pinfunction "-IN_6") (pintype "input"))
      (node (ref "IC8") (pin "7") (pinfunction "OUT_7") (pintype "output"))
      (node (ref "R38") (pin "1") (pinfunction "1_1") (pintype "passive"))
    )
    (net (code "65") (name "Net-(MIDI_T-Pad1)") (class "Default")
      (node (ref "MIDI_T") (pin "1") (pinfunction "1_1") (pintype "passive"))
      (node (ref "R37") (pin "1") (pinfunction "1_1") (pintype "passive"))
    )
    (net (code "66") (name "Net-(Q1-PadB)") (class "Default")
      (node (ref "Q1") (pin "B") (pinfunction "B_B") (pintype "passive"))
      (node (ref "R27") (pin "1") (pinfunction "1_1") (pintype "passive"))
    )
    (net (code "67") (name "Net-(Q1-PadC)") (class "Default")
      (node (ref "Q1") (pin "C") (pinfunction "C_C") (pintype "passive"))
      (node (ref "R31") (pin "1") (pinfunction "1_1") (pintype "passive"))
    )
    (net (code "68") (name "Net-(Q2-PadB)") (class "Default")
      (node (ref "Q2") (pin "B") (pinfunction "B_B") (pintype "passive"))
      (node (ref "R28") (pin "1") (pinfunction "1_1") (pintype "passive"))
    )
    (net (code "69") (name "Net-(Q2-PadC)") (class "Default")
      (node (ref "Q2") (pin "C") (pinfunction "C_C") (pintype "passive"))
      (node (ref "R32") (pin "1") (pinfunction "1_1") (pintype "passive"))
    )
    (net (code "70") (name "Net-(Q3-PadB)") (class "Default")
      (node (ref "Q3") (pin "B") (pinfunction "B_B") (pintype "passive"))
      (node (ref "R29") (pin "1") (pinfunction "1_1") (pintype "passive"))
    )
    (net (code "71") (name "Net-(Q3-PadC)") (class "Default")
      (node (ref "Q3") (pin "C") (pinfunction "C_C") (pintype "passive"))
      (node (ref "R33") (pin "1") (pinfunction "1_1") (pintype "passive"))
    )
    (net (code "72") (name "Net-(Q4-PadB)") (class "Default")
      (node (ref "Q4") (pin "B") (pinfunction "B_B") (pintype "passive"))
      (node (ref "R30") (pin "1") (pinfunction "1_1") (pintype "passive"))
    )
    (net (code "73") (name "Net-(Q4-PadC)") (class "Default")
      (node (ref "Q4") (pin "C") (pinfunction "C_C") (pintype "passive"))
      (node (ref "R34") (pin "1") (pinfunction "1_1") (pintype "passive"))
    )
    (net (code "74") (name "Net-(Q5-PadB)") (class "Default")
      (node (ref "Q5") (pin "B") (pinfunction "B_B") (pintype "passive"))
      (node (ref "R31") (pin "2") (pinfunction "2_2") (pintype "passive"))
    )
    (net (code "75") (name "Net-(Q5-PadC)") (class "Default")
      (node (ref "Q5") (pin "C") (pinfunction "C_C") (pintype "passive"))
      (node (ref "SRC2") (pin "1") (pinfunction "1_1") (pintype "passive"))
    )
    (net (code "76") (name "Net-(Q6-PadB)") (class "Default")
      (node (ref "Q6") (pin "B") (pinfunction "B_B") (pintype "passive"))
      (node (ref "R32") (pin "2") (pinfunction "2_2") (pintype "passive"))
    )
    (net (code "77") (name "Net-(Q6-PadC)") (class "Default")
      (node (ref "Q6") (pin "C") (pinfunction "C_C") (pintype "passive"))
      (node (ref "SRC3") (pin "1") (pinfunction "1_1") (pintype "passive"))
    )
    (net (code "78") (name "Net-(Q7-PadB)") (class "Default")
      (node (ref "Q7") (pin "B") (pinfunction "B_B") (pintype "passive"))
      (node (ref "R33") (pin "2") (pinfunction "2_2") (pintype "passive"))
    )
    (net (code "79") (name "Net-(Q7-PadC)") (class "Default")
      (node (ref "Q7") (pin "C") (pinfunction "C_C") (pintype "passive"))
      (node (ref "SRC1") (pin "1") (pinfunction "1_1") (pintype "passive"))
    )
    (net (code "80") (name "Net-(Q8-PadB)") (class "Default")
      (node (ref "Q8") (pin "B") (pinfunction "B_B") (pintype "passive"))
      (node (ref "R34") (pin "2") (pinfunction "2_2") (pintype "passive"))
    )
    (net (code "81") (name "Net-(Q8-PadC)") (class "Default")
      (node (ref "Q8") (pin "C") (pinfunction "C_C") (pintype "passive"))
      (node (ref "SRC4") (pin "1") (pinfunction "1_1") (pintype "passive"))
    )
    (net (code "82") (name "Net-(R1-Pad1)") (class "Default")
      (node (ref "R1") (pin "1") (pinfunction "1_1") (pintype "passive"))
      (node (ref "SINK1") (pin "1") (pinfunction "1_1") (pintype "passive"))
    )
    (net (code "83") (name "Net-(R2-Pad1)") (class "Default")
      (node (ref "R2") (pin "1") (pinfunction "1_1") (pintype "passive"))
      (node (ref "SINK2") (pin "1") (pinfunction "1_1") (pintype "passive"))
    )
    (net (code "84") (name "Net-(R3-Pad1)") (class "Default")
      (node (ref "R3") (pin "1") (pinfunction "1_1") (pintype "passive"))
      (node (ref "SINK3") (pin "1") (pinfunction "1_1") (pintype "passive"))
    )
    (net (code "85") (name "Net-(R4-Pad1)") (class "Default")
      (node (ref "R4") (pin "1") (pinfunction "1_1") (pintype "passive"))
      (node (ref "SINK4") (pin "1") (pinfunction "1_1") (pintype "passive"))
    )
    (net (code "86") (name "Net-(R5-Pad2)") (class "Default")
      (node (ref "R5") (pin "2") (pinfunction "2_2") (pintype "passive"))
      (node (ref "SINK5") (pin "1") (pinfunction "1_1") (pintype "passive"))
    )
    (net (code "87") (name "Net-(R6-Pad2)") (class "Default")
      (node (ref "R6") (pin "2") (pinfunction "2_2") (pintype "passive"))
      (node (ref "SINK6") (pin "1") (pinfunction "1_1") (pintype "passive"))
    )
    (net (code "88") (name "Net-(R7-Pad2)") (class "Default")
      (node (ref "R7") (pin "2") (pinfunction "2_2") (pintype "passive"))
      (node (ref "SINK7") (pin "1") (pinfunction "1_1") (pintype "passive"))
    )
    (net (code "89") (name "Net-(R8-Pad2)") (class "Default")
      (node (ref "R8") (pin "2") (pinfunction "2_2") (pintype "passive"))
      (node (ref "SINK8") (pin "1") (pinfunction "1_1") (pintype "passive"))
    )
    (net (code "90") (name "Net-(R9-Pad2)") (class "Default")
      (node (ref "R9") (pin "2") (pinfunction "2_2") (pintype "passive"))
      (node (ref "VR1") (pin "E") (pinfunction "E_E") (pintype "passive"))
    )
    (net (code "91") (name "Net-(R10-Pad2)") (class "Default")
      (node (ref "R10") (pin "2") (pinfunction "2_2") (pintype "passive"))
      (node (ref "VR2") (pin "E") (pinfunction "E_E") (pintype "passive"))
    )
    (net (code "92") (name "Net-(R15-Pad1)") (class "Default")
      (node (ref "R15") (pin "1") (pinfunction "1_1") (pintype "passive"))
      (node (ref "VR1") (pin "A") (pinfunction "A_A") (pintype "passive"))
    )
    (net (code "93") (name "Net-(R16-Pad1)") (class "Default")
      (node (ref "R16") (pin "1") (pinfunction "1_1") (pintype "passive"))
      (node (ref "VR2") (pin "A") (pinfunction "A_A") (pintype "passive"))
    )
    (net (code "94") (name "Net-(R39-Pad2)") (class "Default")
      (node (ref "R39") (pin "2") (pinfunction "2_2") (pintype "passive"))
      (node (ref "TRGOUT") (pin "1") (pinfunction "1_1") (pintype "passive"))
    )
    (net (code "95") (name "unconnected-(IC1-Q7S-Pad9)") (class "Default")
      (node (ref "IC1") (pin "9") (pinfunction "Q7S_9") (pintype "output"))
    )
    (net (code "96") (name "unconnected-(IC4-READY-Pad5)") (class "Default")
      (node (ref "IC4") (pin "5") (pinfunction "READY_5") (pintype "bidirectional"))
    )
    (net (code "97") (name "unconnected-(J1-LVP-Pad6)") (class "Default")
      (node (ref "J1") (pin "6") (pinfunction "LVP_6") (pintype "bidirectional"))
    )
  )
)
